# vga.net
KiCad netlist of a schematic drawn in EAGLE
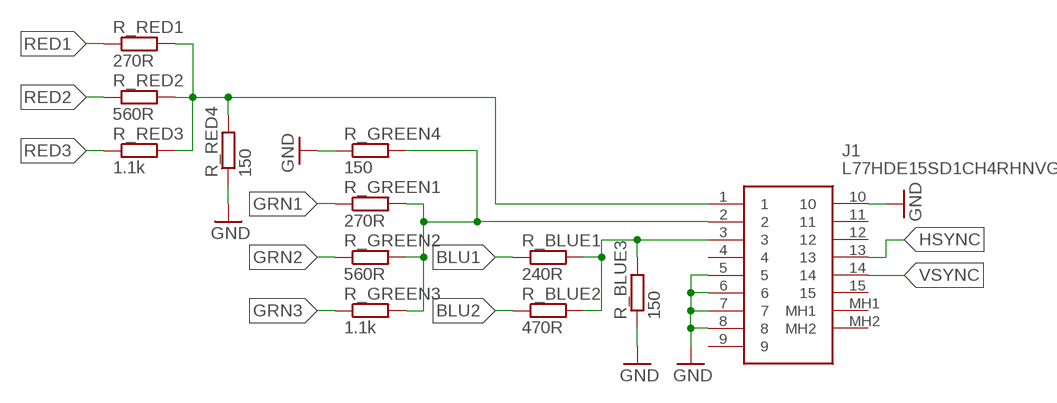
[diagram p0: schematic, sheet 1]

(export (version "E")
  (design (tool "Eeschema 10.0.6"))
  (components
    (comp (ref "J1")
      (value "L77HDE15SD1CH4RHNVGA")
      (footprint "eagle-import:L77HDE15SD1CH4RHNVGA")
      (fields (field (name "MOUSER_PART_NUMBER") "523-7HDE15SDH4RHNVGA"))
      (libsource (lib "eagle-import") (part "L77HDE15SD1CH4RHNVGA"))
    )
    (comp (ref "R_BLUE1")
      (value "240R")
      (footprint "eagle-import:R0805")
      (libsource (lib "eagle-import") (part "R-EU_R0805"))
    )
    (comp (ref "R_BLUE2")
      (value "470R")
      (footprint "eagle-import:R0805")
      (libsource (lib "eagle-import") (part "R-EU_R0805"))
    )
    (comp (ref "R_BLUE3")
      (value "150")
      (footprint "eagle-import:R0805")
      (libsource (lib "eagle-import") (part "R-EU_R0805"))
    )
    (comp (ref "R_GREEN1")
      (value "270R")
      (footprint "eagle-import:R0805")
      (libsource (lib "eagle-import") (part "R-EU_R0805"))
    )
    (comp (ref "R_GREEN2")
      (value "560R")
      (footprint "eagle-import:R0805")
      (libsource (lib "eagle-import") (part "R-EU_R0805"))
    )
    (comp (ref "R_GREEN3")
      (value "1.1k")
      (footprint "eagle-import:R0805")
      (libsource (lib "eagle-import") (part "R-EU_R0805"))
    )
    (comp (ref "R_GREEN4")
      (value "150")
      (footprint "eagle-import:R0805")
      (libsource (lib "eagle-import") (part "R-EU_R0805"))
    )
    (comp (ref "R_RED1")
      (value "270R")
      (footprint "eagle-import:R0805")
      (libsource (lib "eagle-import") (part "R-EU_R0805"))
    )
    (comp (ref "R_RED2")
      (value "560R")
      (footprint "eagle-import:R0805")
      (libsource (lib "eagle-import") (part "R-EU_R0805"))
    )
    (comp (ref "R_RED3")
      (value "1.1k")
      (footprint "eagle-import:R0805")
      (libsource (lib "eagle-import") (part "R-EU_R0805"))
    )
    (comp (ref "R_RED4")
      (value "150")
      (footprint "eagle-import:R0805")
      (libsource (lib "eagle-import") (part "R-EU_R0805"))
    )
  )
  (nets
    (net (code "1") (name "BLU1") (class "Default")
      (node (ref "R_BLUE1") (pin "1") (pinfunction "1_1") (pintype "passive"))
    )
    (net (code "2") (name "BLU2") (class "Default")
      (node (ref "R_BLUE2") (pin "1") (pinfunction "1_1") (pintype "passive"))
    )
    (net (code "3") (name "GND") (class "Default")
      (node (ref "J1") (pin "10") (pinfunction "10_10") (pintype "bidirectional"))
      (node (ref "J1") (pin "5") (pinfunction "5_5") (pintype "bidirectional"))
      (node (ref "J1") (pin "6") (pinfunction "6_6") (pintype "bidirectional"))
      (node (ref "J1") (pin "7") (pinfunction "7_7") (pintype "bidirectional"))
      (node (ref "J1") (pin "8") (pinfunction "8_8") (pintype "bidirectional"))
      (node (ref "R_BLUE3") (pin "1") (pinfunction "1_1") (pintype "passive"))
      (node (ref "R_GREEN4") (pin "1") (pinfunction "1_1") (pintype "passive"))
      (node (ref "R_RED4") (pin "1") (pinfunction "1_1") (pintype "passive"))
    )
    (net (code "4") (name "GRN1") (class "Default")
      (node (ref "R_GREEN1") (pin "1") (pinfunction "1_1") (pintype "passive"))
    )
    (net (code "5") (name "GRN2") (class "Default")
      (node (ref "R_GREEN2") (pin "1") (pinfunction "1_1") (pintype "passive"))
    )
    (net (code "6") (name "GRN3") (class "Default")
      (node (ref "R_GREEN3") (pin "1") (pinfunction "1_1") (pintype "passive"))
    )
    (net (code "7") (name "HSYNC") (class "Default")
      (node (ref "J1") (pin "13") (pinfunction "13_13") (pintype "bidirectional"))
    )
    (net (code "8") (name "Net-(J1-Pad1)") (class "Default")
      (node (ref "J1") (pin "1") (pinfunction "1_1") (pintype "bidirectional"))
      (node (ref "R_RED1") (pin "2") (pinfunction "2_2") (pintype "passive"))
      (node (ref "R_RED2") (pin "2") (pinfunction "2_2") (pintype "passive"))
      (node (ref "R_RED3") (pin "2") (pinfunction "2_2") (pintype "passive"))
      (node (ref "R_RED4") (pin "2") (pinfunction "2_2") (pintype "passive"))
    )
    (net (code "9") (name "Net-(J1-Pad2)") (class "Default")
      (node (ref "J1") (pin "2") (pinfunction "2_2") (pintype "bidirectional"))
      (node (ref "R_GREEN1") (pin "2") (pinfunction "2_2") (pintype "passive"))
      (node (ref "R_GREEN2") (pin "2") (pinfunction "2_2") (pintype "passive"))
      (node (ref "R_GREEN3") (pin "2") (pinfunction "2_2") (pintype "passive"))
      (node (ref "R_GREEN4") (pin "2") (pinfunction "2_2") (pintype "passive"))
    )
    (net (code "10") (name "Net-(J1-Pad3)") (class "Default")
      (node (ref "J1") (pin "3") (pinfunction "3_3") (pintype "bidirectional"))
      (node (ref "R_BLUE1") (pin "2") (pinfunction "2_2") (pintype "passive"))
      (node (ref "R_BLUE2") (pin "2") (pinfunction "2_2") (pintype "passive"))
      (node (ref "R_BLUE3") (pin "2") (pinfunction "2_2") (pintype "passive"))
    )
    (net (code "11") (name "RED1") (class "Default")
      (node (ref "R_RED1") (pin "1") (pinfunction "1_1") (pintype "passive"))
    )
    (net (code "12") (name "RED2") (class "Default")
      (node (ref "R_RED2") (pin "1") (pinfunction "1_1") (pintype "passive"))
    )
    (net (code "13") (name "RED3") (class "Default")
      (node (ref "R_RED3") (pin "1") (pinfunction "1_1") (pintype "passive"))
    )
    (net (code "14") (name "VSYNC") (class "Default")
      (node (ref "J1") (pin "14") (pinfunction "14_14") (pintype "bidirectional"))
    )
    (net (code "15") (name "unconnected-(J1-Pad4)") (class "Default")
      (node (ref "J1") (pin "4") (pinfunction "4_4") (pintype "bidirectional"))
    )
    (net (code "16") (name "unconnected-(J1-Pad9)") (class "Default")
      (node (ref "J1") (pin "9") (pinfunction "9_9") (pintype "bidirectional"))
    )
    (net (code "17") (name "unconnected-(J1-Pad11)") (class "Default")
      (node (ref "J1") (pin "11") (pinfunction "11_11") (pintype "bidirectional"))
    )
    (net (code "18") (name "unconnected-(J1-Pad12)") (class "Default")
      (node (ref "J1") (pin "12") (pinfunction "12_12") (pintype "bidirectional"))
    )
    (net (code "19") (name "unconnected-(J1-Pad15)") (class "Default")
      (node (ref "J1") (pin "15") (pinfunction "15_15") (pintype "bidirectional"))
    )
    (net (code "20") (name "unconnected-(J1-PadMH1)") (class "Default")
      (node (ref "J1") (pin "MH1") (pinfunction "MH1_MH1") (pintype "bidirectional"))
    )
    (net (code "21") (name "unconnected-(J1-PadMH2)") (class "Default")
      (node (ref "J1") (pin "MH2") (pinfunction "MH2_MH2") (pintype "bidirectional"))
    )
  )
)
